# hsweg01-v0_3_1.net
KiCad netlist of a schematic drawn in EAGLE
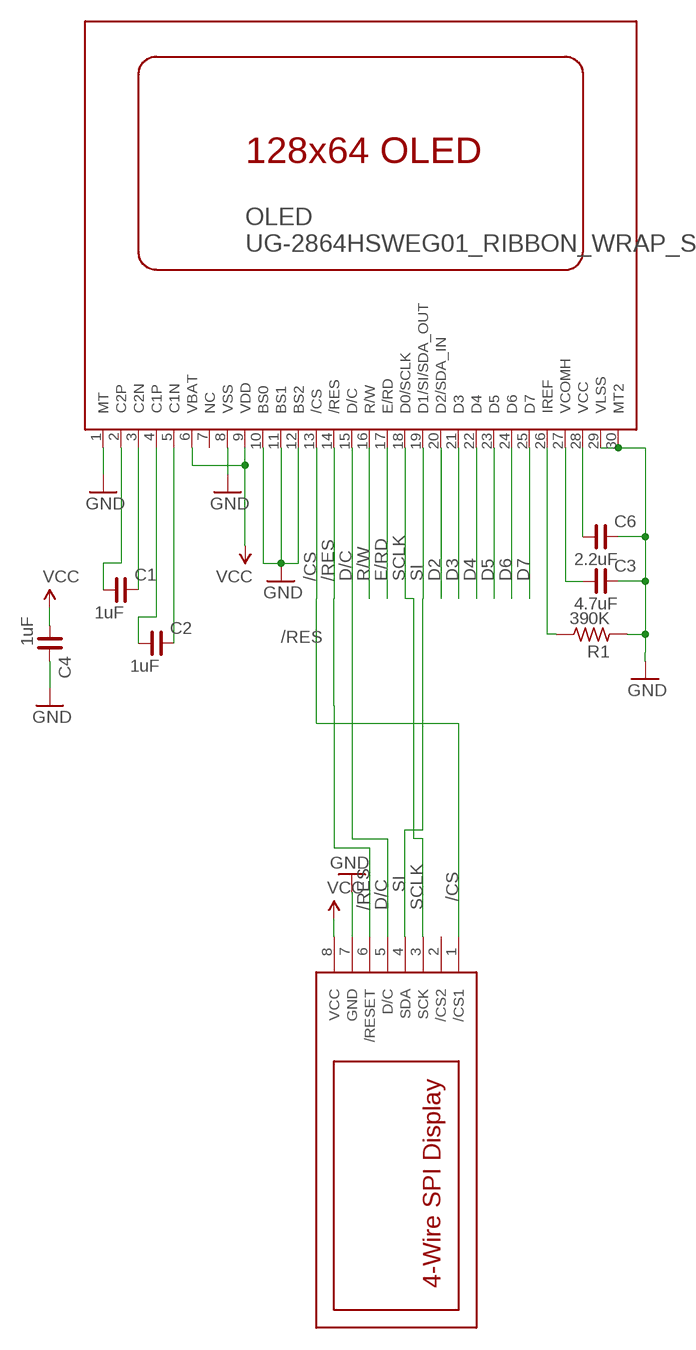
[diagram p0: schematic, sheet 1]

(export (version "E")
  (design (tool "Eeschema 10.0.6"))
  (components
    (comp (ref "C1")
      (value "1uF")
      (footprint "eagle-import:C0603")
      (libsource (lib "eagle-import") (part "C_0603"))
    )
    (comp (ref "C2")
      (value "1uF")
      (footprint "eagle-import:C0603")
      (libsource (lib "eagle-import") (part "C_0603"))
    )
    (comp (ref "C3")
      (value "4.7uF")
      (footprint "eagle-import:C0805")
      (libsource (lib "eagle-import") (part "C_0805"))
    )
    (comp (ref "C4")
      (value "1uF")
      (footprint "eagle-import:C0603")
      (libsource (lib "eagle-import") (part "C_0603"))
    )
    (comp (ref "C6")
      (value "2.2uF")
      (footprint "eagle-import:C0805")
      (libsource (lib "eagle-import") (part "C_0805"))
    )
    (comp (ref "OLED")
      (value "UG-2864HSWEG01_RIBBON_WRAP_SILK")
      (footprint "eagle-import:UG-2864HSWEG01")
      (libsource (lib "eagle-import") (part "UG-2864HSWEG01_RIBBON_WRAP_SILK"))
    )
    (comp (ref "R1")
      (value "390K")
      (footprint "eagle-import:R0603")
      (libsource (lib "eagle-import") (part "R_0603"))
    )
    (comp (ref "U$1")
      (value "4W-SPI-DISP")
      (footprint "eagle-import:1X08-NOSILK")
      (libsource (lib "eagle-import") (part "4W-SPI-DISP"))
    )
  )
  (nets
    (net (code "1") (name "/D2") (class "Default")
      (node (ref "OLED") (pin "20") (pinfunction "D2/SDA_IN_20") (pintype "bidirectional"))
    )
    (net (code "2") (name "/D3") (class "Default")
      (node (ref "OLED") (pin "21") (pinfunction "D3_21") (pintype "bidirectional"))
    )
    (net (code "3") (name "/D4") (class "Default")
      (node (ref "OLED") (pin "22") (pinfunction "D4_22") (pintype "bidirectional"))
    )
    (net (code "4") (name "/D5") (class "Default")
      (node (ref "OLED") (pin "23") (pinfunction "D5_23") (pintype "bidirectional"))
    )
    (net (code "5") (name "/D6") (class "Default")
      (node (ref "OLED") (pin "24") (pinfunction "D6_24") (pintype "bidirectional"))
    )
    (net (code "6") (name "/D7") (class "Default")
      (node (ref "OLED") (pin "25") (pinfunction "D7_25") (pintype "bidirectional"))
    )
    (net (code "7") (name "/D{slash}C") (class "Default")
      (node (ref "OLED") (pin "15") (pinfunction "D/C_15") (pintype "input"))
      (node (ref "U$1") (pin "5") (pinfunction "D/C_5") (pintype "bidirectional"))
    )
    (net (code "8") (name "/E{slash}RD") (class "Default")
      (node (ref "OLED") (pin "17") (pinfunction "E/RD_17") (pintype "input"))
    )
    (net (code "9") (name "/R{slash}W") (class "Default")
      (node (ref "OLED") (pin "16") (pinfunction "R/W_16") (pintype "input"))
    )
    (net (code "10") (name "/SCLK") (class "Default")
      (node (ref "OLED") (pin "18") (pinfunction "D0/SCLK_18") (pintype "bidirectional"))
      (node (ref "U$1") (pin "3") (pinfunction "SCK_3") (pintype "bidirectional"))
    )
    (net (code "11") (name "/SI") (class "Default")
      (node (ref "OLED") (pin "19") (pinfunction "D1/SI/SDA_OUT_19") (pintype "bidirectional"))
      (node (ref "U$1") (pin "4") (pinfunction "SDA_4") (pintype "bidirectional"))
    )
    (net (code "12") (name "/{slash}CS") (class "Default")
      (node (ref "OLED") (pin "13") (pinfunction "/CS_13") (pintype "input"))
      (node (ref "U$1") (pin "1") (pinfunction "/CS1_1") (pintype "bidirectional"))
    )
    (net (code "13") (name "/{slash}RES") (class "Default")
      (node (ref "OLED") (pin "14") (pinfunction "/RES_14") (pintype "input"))
      (node (ref "U$1") (pin "6") (pinfunction "/RESET_6") (pintype "bidirectional"))
    )
    (net (code "14") (name "GND") (class "Default")
      (node (ref "C3") (pin "2") (pinfunction "2_2") (pintype "passive"))
      (node (ref "C4") (pin "2") (pinfunction "2_2") (pintype "passive"))
      (node (ref "C6") (pin "2") (pinfunction "2_2") (pintype "passive"))
      (node (ref "OLED") (pin "1") (pinfunction "MT_1") (pintype "input"))
      (node (ref "OLED") (pin "10") (pinfunction "BS0_10") (pintype "input"))
      (node (ref "OLED") (pin "11") (pinfunction "BS1_11") (pintype "input"))
      (node (ref "OLED") (pin "12") (pinfunction "BS2_12") (pintype "input"))
      (node (ref "OLED") (pin "29") (pinfunction "VLSS_29") (pintype "power_in"))
      (node (ref "OLED") (pin "30") (pinfunction "MT2_30") (pintype "input"))
      (node (ref "OLED") (pin "8") (pinfunction "VSS_8") (pintype "power_in"))
      (node (ref "R1") (pin "1") (pinfunction "1_1") (pintype "passive"))
      (node (ref "U$1") (pin "7") (pinfunction "GND_7") (pintype "power_in"))
    )
    (net (code "15") (name "Net-(OLED-C1N)") (class "Default")
      (node (ref "C2") (pin "2") (pinfunction "2_2") (pintype "passive"))
      (node (ref "OLED") (pin "5") (pinfunction "C1N_5") (pintype "input"))
    )
    (net (code "16") (name "Net-(OLED-C1P)") (class "Default")
      (node (ref "C2") (pin "1") (pinfunction "1_1") (pintype "passive"))
      (node (ref "OLED") (pin "4") (pinfunction "C1P_4") (pintype "input"))
    )
    (net (code "17") (name "Net-(OLED-C2N)") (class "Default")
      (node (ref "C1") (pin "2") (pinfunction "2_2") (pintype "passive"))
      (node (ref "OLED") (pin "3") (pinfunction "C2N_3") (pintype "input"))
    )
    (net (code "18") (name "Net-(OLED-C2P)") (class "Default")
      (node (ref "C1") (pin "1") (pinfunction "1_1") (pintype "passive"))
      (node (ref "OLED") (pin "2") (pinfunction "C2P_2") (pintype "input"))
    )
    (net (code "19") (name "Net-(OLED-IREF)") (class "Default")
      (node (ref "OLED") (pin "26") (pinfunction "IREF_26") (pintype "input"))
      (node (ref "R1") (pin "2") (pinfunction "2_2") (pintype "passive"))
    )
    (net (code "20") (name "Net-(OLED-VCC)") (class "Default")
      (node (ref "C6") (pin "1") (pinfunction "1_1") (pintype "passive"))
      (node (ref "OLED") (pin "28") (pinfunction "VCC_28") (pintype "power_in"))
    )
    (net (code "21") (name "Net-(OLED-VCOMH)") (class "Default")
      (node (ref "C3") (pin "1") (pinfunction "1_1") (pintype "passive"))
      (node (ref "OLED") (pin "27") (pinfunction "VCOMH_27") (pintype "output"))
    )
    (net (code "22") (name "VCC") (class "Default")
      (node (ref "C4") (pin "1") (pinfunction "1_1") (pintype "passive"))
      (node (ref "OLED") (pin "6") (pinfunction "VBAT_6") (pintype "input"))
      (node (ref "OLED") (pin "9") (pinfunction "VDD_9") (pintype "power_in"))
      (node (ref "U$1") (pin "8") (pinfunction "VCC_8") (pintype "power_in"))
    )
    (net (code "23") (name "unconnected-(OLED-NC-Pad7)") (class "Default")
      (node (ref "OLED") (pin "7") (pinfunction "NC_7") (pintype "no_connect"))
    )
    (net (code "24") (name "unconnected-(U$1-{slash}CS2-Pad2)") (class "Default")
      (node (ref "U$1") (pin "2") (pinfunction "/CS2_2") (pintype "bidirectional"))
    )
  )
)
